# Peripheral.net
KiCad netlist of a schematic drawn in Altium Designer
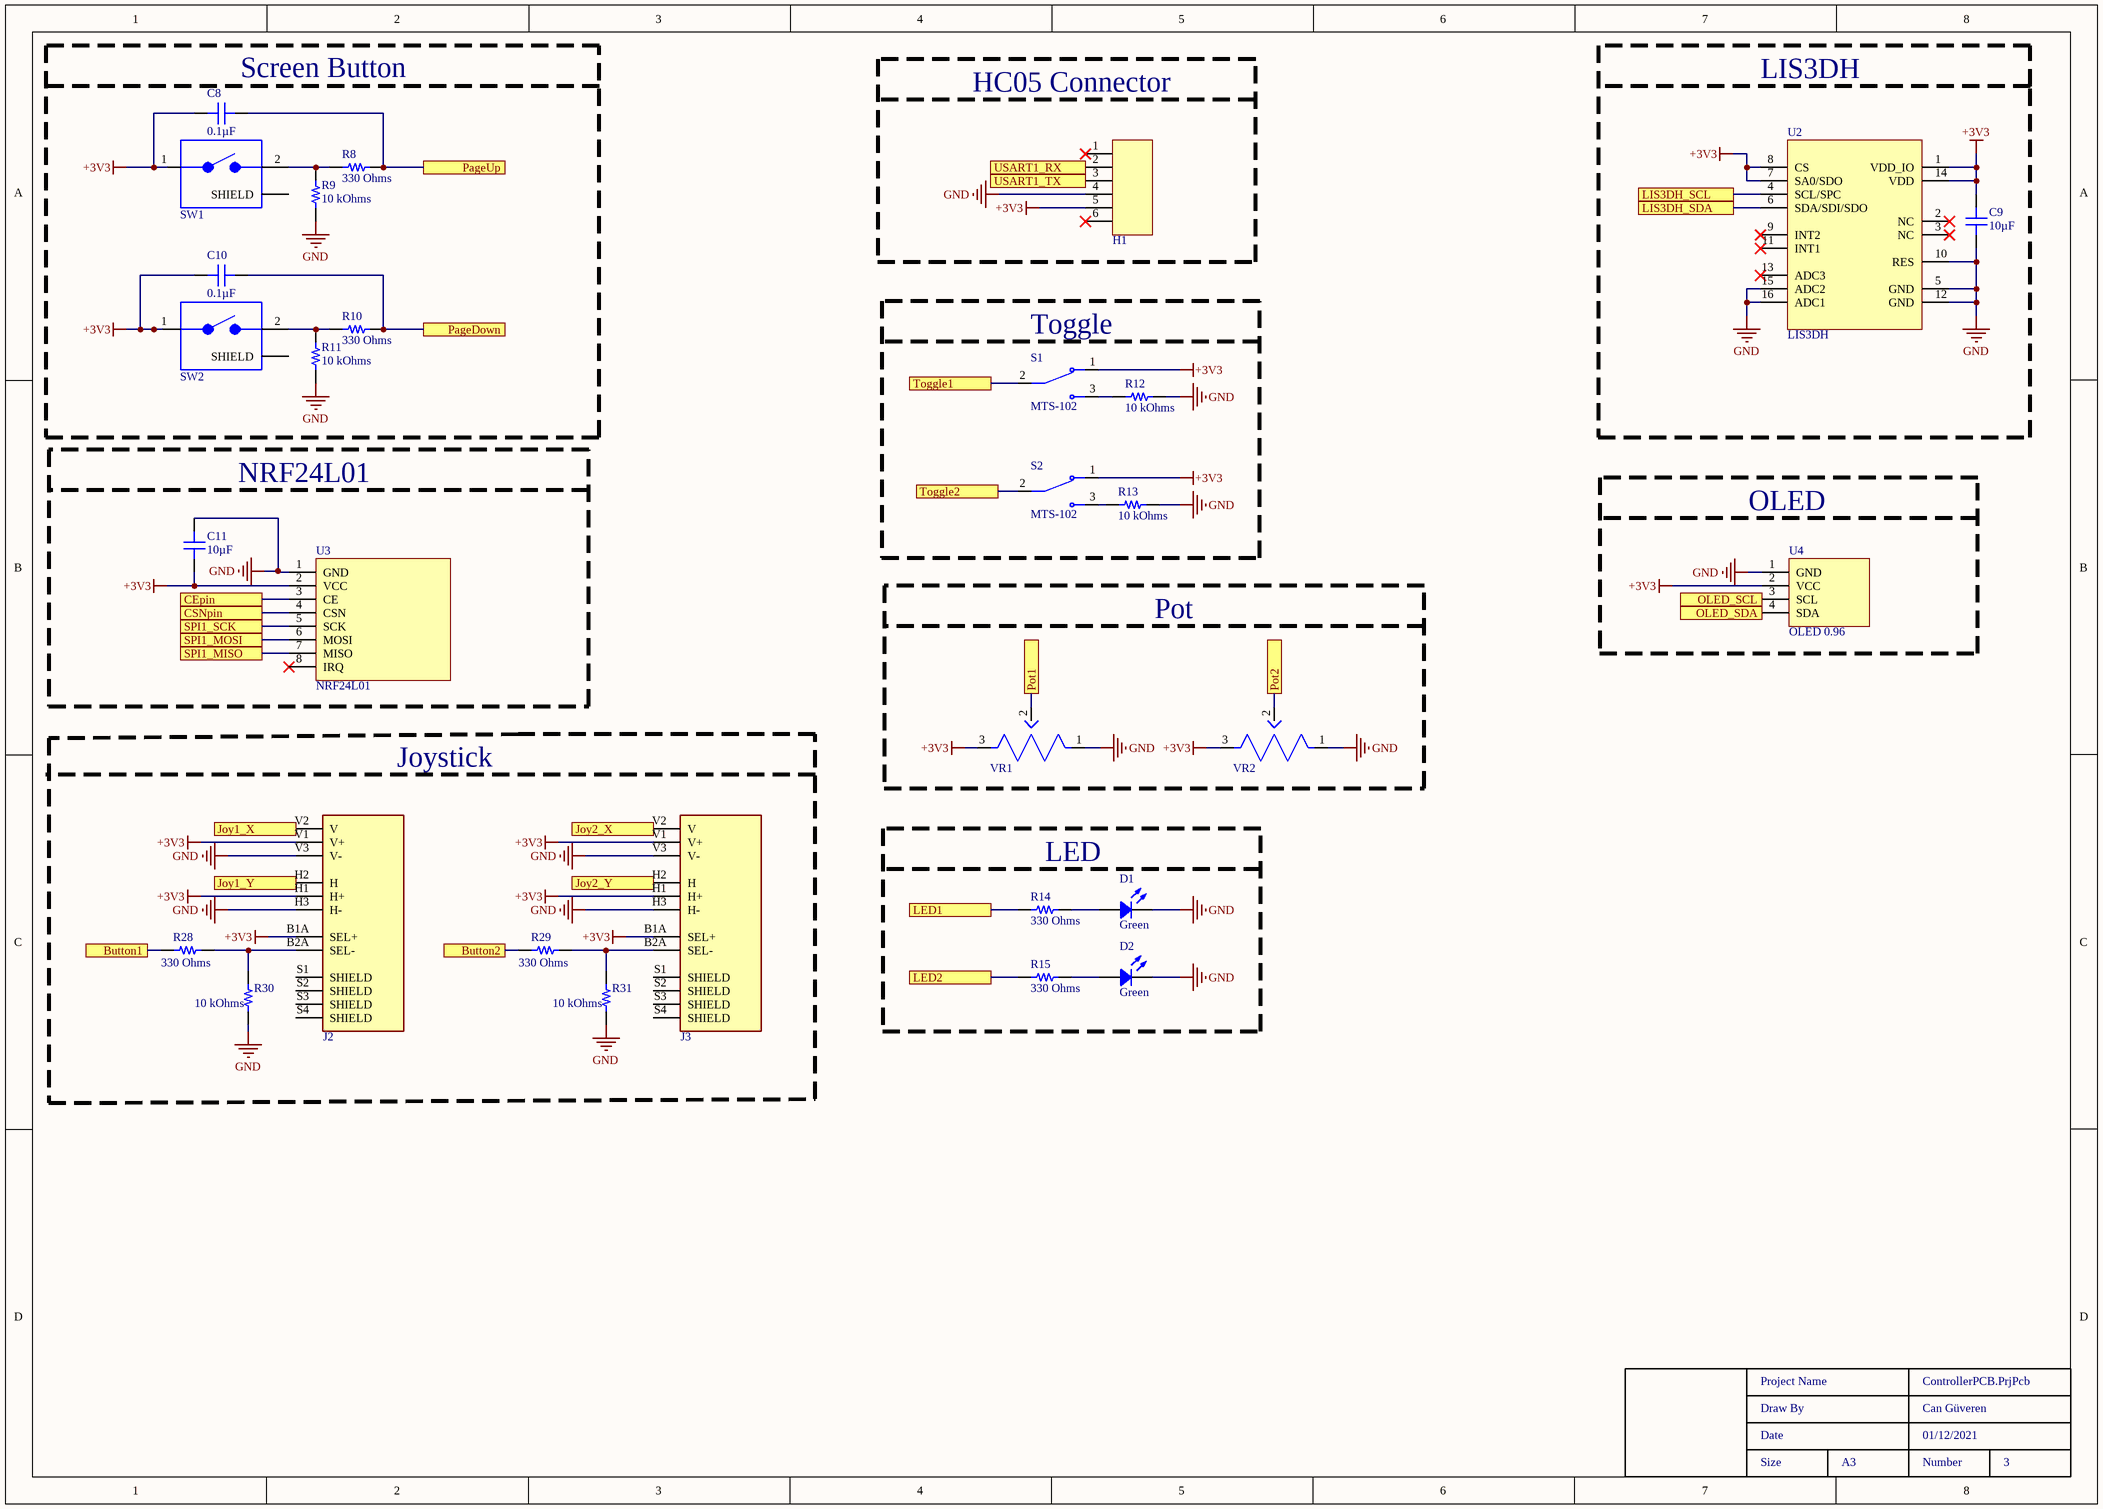
[diagram p0: Peripheral.SchDoc]

(export (version "E")
  (design (tool "Eeschema 10.0.6"))
  (components
    (comp (ref "C8")
      (value "0.1µF")
      (footprint "CAP 0603_1608")
      (description "CAP CER 0.1UF 50V X7R 0603")
      (fields (field (name "PART NUMBER") "C0603C104K5RAC7411") (field (name "MANUFACTURER") "KEMET"))
      (libsource (lib "Celestial Altium Library - altium_library") (part "Capacitor"))
    )
    (comp (ref "C9")
      (value "10µF")
      (footprint "CAP 0603_1608")
      (description "CAP CER 10UF 6.3V X5R 0603")
      (fields
        (field (name "PART NUMBER") "GRM188R60J106ME47D")
        (field (name "MANUFACTURER") "Murata Electronics")
      )
      (libsource (lib "Celestial Altium Library - altium_library") (part "Capacitor"))
    )
    (comp (ref "C10")
      (value "0.1µF")
      (footprint "CAP 0603_1608")
      (description "CAP CER 0.1UF 50V X7R 0603")
      (fields (field (name "PART NUMBER") "C0603C104K5RAC7411") (field (name "MANUFACTURER") "KEMET"))
      (libsource (lib "Celestial Altium Library - altium_library") (part "Capacitor"))
    )
    (comp (ref "C11")
      (value "10µF")
      (footprint "CAP 0603_1608")
      (description "CAP CER 10UF 6.3V X5R 0603")
      (fields
        (field (name "PART NUMBER") "GRM188R60J106ME47D")
        (field (name "MANUFACTURER") "Murata Electronics")
      )
      (libsource (lib "Celestial Altium Library - altium_library") (part "Capacitor"))
    )
    (comp (ref "D1")
      (value "Green")
      (footprint "LED 1206_3216 YELLOW")
      (description "LED YELLOW 1206 SMD")
      (fields (field (name "PART NUMBER") "5990240007F") (field (name "MANUFACTURER") "Dialight"))
      (libsource (lib "Celestial Altium Library - altium_library") (part "LED"))
    )
    (comp (ref "D2")
      (value "Green")
      (footprint "LED 1206_3216 YELLOW")
      (description "LED YELLOW 1206 SMD")
      (fields (field (name "PART NUMBER") "5990240007F") (field (name "MANUFACTURER") "Dialight"))
      (libsource (lib "Celestial Altium Library - altium_library") (part "LED"))
    )
    (comp (ref "H1")
      (value "1x6 Pin Header - Female")
      (footprint "1x6 Pin Header - Female")
      (libsource (lib "MyLibrary_Integrated") (part "1x6 Pin Header - Female"))
    )
    (comp (ref "J2")
      (value "COM-09032")
      (footprint "COM-09032")
      (description "Joystick 10K Ohm 2 Axis Th")
      (fields (field (name "MANUFACTURER") "SparkFun"))
      (libsource (lib "MyLibrary_Integrated") (part "COM-09032"))
    )
    (comp (ref "J3")
      (value "COM-09032")
      (footprint "COM-09032")
      (description "Joystick 10K Ohm 2 Axis Th")
      (fields (field (name "MANUFACTURER") "SparkFun"))
      (libsource (lib "MyLibrary_Integrated") (part "COM-09032"))
    )
    (comp (ref "R8")
      (value "330 Ohms")
      (footprint "RES 0603_1608")
      (description "RES SMD 330 OHM 1% 1/10W 0603")
      (fields (field (name "PART NUMBER") "AC0603FR-07330RL") (field (name "MANUFACTURER") "Yageo"))
      (libsource (lib "Celestial Altium Library - altium_library") (part "Resistor"))
    )
    (comp (ref "R9")
      (value "10 kOhms")
      (footprint "RES 0603_1608")
      (description "RES 10K OHM 0.1% 1/16W 0603")
      (fields
        (field (name "PART NUMBER") "RNCS0603BKE10K0")
        (field (name "MANUFACTURER") "Stackpole Electronics Inc")
      )
      (libsource (lib "Celestial Altium Library - altium_library") (part "Resistor"))
    )
    (comp (ref "R10")
      (value "330 Ohms")
      (footprint "RES 0603_1608")
      (description "RES SMD 330 OHM 1% 1/10W 0603")
      (fields (field (name "PART NUMBER") "AC0603FR-07330RL") (field (name "MANUFACTURER") "Yageo"))
      (libsource (lib "Celestial Altium Library - altium_library") (part "Resistor"))
    )
    (comp (ref "R11")
      (value "10 kOhms")
      (footprint "RES 0603_1608")
      (description "RES 10K OHM 0.1% 1/16W 0603")
      (fields
        (field (name "PART NUMBER") "RNCS0603BKE10K0")
        (field (name "MANUFACTURER") "Stackpole Electronics Inc")
      )
      (libsource (lib "Celestial Altium Library - altium_library") (part "Resistor"))
    )
    (comp (ref "R12")
      (value "10 kOhms")
      (footprint "RES 0603_1608")
      (description "RES 10K OHM 0.1% 1/16W 0603")
      (fields
        (field (name "PART NUMBER") "RNCS0603BKE10K0")
        (field (name "MANUFACTURER") "Stackpole Electronics Inc")
      )
      (libsource (lib "Celestial Altium Library - altium_library") (part "Resistor"))
    )
    (comp (ref "R13")
      (value "10 kOhms")
      (footprint "RES 0603_1608")
      (description "RES 10K OHM 0.1% 1/16W 0603")
      (fields
        (field (name "PART NUMBER") "RNCS0603BKE10K0")
        (field (name "MANUFACTURER") "Stackpole Electronics Inc")
      )
      (libsource (lib "Celestial Altium Library - altium_library") (part "Resistor"))
    )
    (comp (ref "R14")
      (value "330 Ohms")
      (footprint "RES 0603_1608")
      (description "RES SMD 330 OHM 1% 1/10W 0603")
      (fields (field (name "PART NUMBER") "AC0603FR-07330RL") (field (name "MANUFACTURER") "Yageo"))
      (libsource (lib "Celestial Altium Library - altium_library") (part "Resistor"))
    )
    (comp (ref "R15")
      (value "330 Ohms")
      (footprint "RES 0603_1608")
      (description "RES SMD 330 OHM 1% 1/10W 0603")
      (fields (field (name "PART NUMBER") "AC0603FR-07330RL") (field (name "MANUFACTURER") "Yageo"))
      (libsource (lib "Celestial Altium Library - altium_library") (part "Resistor"))
    )
    (comp (ref "R28")
      (value "330 Ohms")
      (footprint "RES 0603_1608")
      (description "RES SMD 330 OHM 1% 1/10W 0603")
      (fields (field (name "PART NUMBER") "AC0603FR-07330RL") (field (name "MANUFACTURER") "Yageo"))
      (libsource (lib "Celestial Altium Library - altium_library") (part "Resistor"))
    )
    (comp (ref "R29")
      (value "330 Ohms")
      (footprint "RES 0603_1608")
      (description "RES SMD 330 OHM 1% 1/10W 0603")
      (fields (field (name "PART NUMBER") "AC0603FR-07330RL") (field (name "MANUFACTURER") "Yageo"))
      (libsource (lib "Celestial Altium Library - altium_library") (part "Resistor"))
    )
    (comp (ref "R30")
      (value "10 kOhms")
      (footprint "RES 0603_1608")
      (description "RES 10K OHM 0.1% 1/16W 0603")
      (fields
        (field (name "PART NUMBER") "RNCS0603BKE10K0")
        (field (name "MANUFACTURER") "Stackpole Electronics Inc")
      )
      (libsource (lib "Celestial Altium Library - altium_library") (part "Resistor"))
    )
    (comp (ref "R31")
      (value "10 kOhms")
      (footprint "RES 0603_1608")
      (description "RES 10K OHM 0.1% 1/16W 0603")
      (fields
        (field (name "PART NUMBER") "RNCS0603BKE10K0")
        (field (name "MANUFACTURER") "Stackpole Electronics Inc")
      )
      (libsource (lib "Celestial Altium Library - altium_library") (part "Resistor"))
    )
    (comp (ref "S1")
      (value "MTS-102")
      (footprint "MTS-102 (Toggle)")
      (libsource (lib "MyLibrary_Integrated") (part "MTS-102"))
    )
    (comp (ref "S2")
      (value "MTS-102")
      (footprint "MTS-102 (Toggle)")
      (libsource (lib "MyLibrary_Integrated") (part "MTS-102"))
    )
    (comp (ref "SW1")
      (value "Switch Tactile, Right Angle")
      (footprint "Tactile Switch")
      (libsource (lib "MyLibrary_Integrated") (part "Switch Tactile, Right Angle"))
    )
    (comp (ref "SW2")
      (value "Switch Tactile, Right Angle")
      (footprint "Tactile Switch")
      (libsource (lib "MyLibrary_Integrated") (part "Switch Tactile, Right Angle"))
    )
    (comp (ref "U2")
      (value "LIS3DH")
      (footprint "VFLGA-16")
      (description "MEMS digital output motion sensor ultra low-power high performance 3-axes \"nano\" accelerometer")
      (fields (field (name "MANUFACTURER") "STMicroelectronics"))
      (libsource (lib "MyLibrary_Integrated") (part "LIS3DH"))
    )
    (comp (ref "U3")
      (value "NRF24L01")
      (footprint "NRF24L01+ PCB")
      (libsource (lib "MyLibrary_Integrated") (part "NRF24L01+ PCB"))
    )
    (comp (ref "U4")
      (value "OLED 0.96")
      (footprint "OLED 0.96")
      (libsource (lib "MyLibrary_Integrated") (part "OLED 0.96"))
    )
    (comp (ref "VR1")
      (value "PTV09A-4225F-B104")
      (footprint "PTV09A-4225F-B104")
      (fields (field (name "MANUFACTURER") "Bourns") (field (name "TOLERANCE") "20%"))
      (libsource (lib "MyLibrary_Integrated") (part "PTV09A-4225F-B104"))
    )
    (comp (ref "VR2")
      (value "PTV09A-4225F-B104")
      (footprint "PTV09A-4225F-B104")
      (fields (field (name "MANUFACTURER") "Bourns") (field (name "TOLERANCE") "20%"))
      (libsource (lib "MyLibrary_Integrated") (part "PTV09A-4225F-B104"))
    )
  )
  (nets
    (net (code "1") (name "+3V3") (class "Default")
      (node (ref "C10") (pin "1") (pinfunction "1_1") (pintype "passive"))
      (node (ref "C11") (pin "1") (pinfunction "1_1") (pintype "passive"))
      (node (ref "C8") (pin "1") (pinfunction "1_1") (pintype "passive"))
      (node (ref "C9") (pin "2") (pinfunction "2_2") (pintype "passive"))
      (node (ref "H1") (pin "5") (pinfunction "4_5") (pintype "passive"))
      (node (ref "J2") (pin "B1A") (pinfunction "SEL+_B1A") (pintype "passive"))
      (node (ref "J2") (pin "H1") (pinfunction "H+_H1") (pintype "passive"))
      (node (ref "J2") (pin "V1") (pinfunction "V+_V1") (pintype "passive"))
      (node (ref "J3") (pin "B1A") (pinfunction "SEL+_B1A") (pintype "passive"))
      (node (ref "J3") (pin "H1") (pinfunction "H+_H1") (pintype "passive"))
      (node (ref "J3") (pin "V1") (pinfunction "V+_V1") (pintype "passive"))
      (node (ref "S1") (pin "1") (pinfunction "1_1") (pintype "passive"))
      (node (ref "S2") (pin "1") (pinfunction "1_1") (pintype "passive"))
      (node (ref "SW1") (pin "1") (pinfunction "1_1") (pintype "passive"))
      (node (ref "SW2") (pin "1") (pinfunction "1_1") (pintype "passive"))
      (node (ref "U2") (pin "1") (pinfunction "VDD_IO_1") (pintype "passive"))
      (node (ref "U2") (pin "14") (pinfunction "VDD_14") (pintype "passive"))
      (node (ref "U2") (pin "7") (pinfunction "SA0/SDO_7") (pintype "passive"))
      (node (ref "U2") (pin "8") (pinfunction "CS_8") (pintype "passive"))
      (node (ref "U3") (pin "2") (pinfunction "VCC_2") (pintype "passive"))
      (node (ref "U4") (pin "2") (pinfunction "VCC_2") (pintype "passive"))
      (node (ref "VR1") (pin "3") (pinfunction "3_3") (pintype "passive"))
      (node (ref "VR2") (pin "3") (pinfunction "3_3") (pintype "passive"))
    )
    (net (code "2") (name "/Button1") (class "Default")
      (node (ref "R28") (pin "1") (pinfunction "1_1") (pintype "passive"))
    )
    (net (code "3") (name "/Button2") (class "Default")
      (node (ref "R29") (pin "1") (pinfunction "1_1") (pintype "passive"))
    )
    (net (code "4") (name "/CEpin") (class "Default")
      (node (ref "U3") (pin "3") (pinfunction "CE_3") (pintype "passive"))
    )
    (net (code "5") (name "/CSNpin") (class "Default")
      (node (ref "U3") (pin "4") (pinfunction "CSN_4") (pintype "passive"))
    )
    (net (code "6") (name "/Joy1_X") (class "Default")
      (node (ref "J2") (pin "V2") (pinfunction "V_V2") (pintype "passive"))
    )
    (net (code "7") (name "/Joy1_Y") (class "Default")
      (node (ref "J2") (pin "H2") (pinfunction "H_H2") (pintype "passive"))
    )
    (net (code "8") (name "/Joy2_X") (class "Default")
      (node (ref "J3") (pin "V2") (pinfunction "V_V2") (pintype "passive"))
    )
    (net (code "9") (name "/Joy2_Y") (class "Default")
      (node (ref "J3") (pin "H2") (pinfunction "H_H2") (pintype "passive"))
    )
    (net (code "10") (name "/LED1") (class "Default")
      (node (ref "R14") (pin "1") (pinfunction "1_1") (pintype "passive"))
    )
    (net (code "11") (name "/LED2") (class "Default")
      (node (ref "R15") (pin "1") (pinfunction "1_1") (pintype "passive"))
    )
    (net (code "12") (name "/LIS3DH_SCL") (class "Default")
      (node (ref "U2") (pin "4") (pinfunction "SCL/SPC_4") (pintype "passive"))
    )
    (net (code "13") (name "/LIS3DH_SDA") (class "Default")
      (node (ref "U2") (pin "6") (pinfunction "SDA/SDI/SDO_6") (pintype "passive"))
    )
    (net (code "14") (name "/OLED_SCL") (class "Default")
      (node (ref "U4") (pin "3") (pinfunction "SCL_3") (pintype "passive"))
    )
    (net (code "15") (name "/OLED_SDA") (class "Default")
      (node (ref "U4") (pin "4") (pinfunction "SDA_4") (pintype "passive"))
    )
    (net (code "16") (name "/PageDown") (class "Default")
      (node (ref "C10") (pin "2") (pinfunction "2_2") (pintype "passive"))
      (node (ref "R10") (pin "2") (pinfunction "2_2") (pintype "passive"))
    )
    (net (code "17") (name "/PageUp") (class "Default")
      (node (ref "C8") (pin "2") (pinfunction "2_2") (pintype "passive"))
      (node (ref "R8") (pin "2") (pinfunction "2_2") (pintype "passive"))
    )
    (net (code "18") (name "/Pot1") (class "Default")
      (node (ref "VR1") (pin "2") (pinfunction "2_2") (pintype "passive"))
    )
    (net (code "19") (name "/Pot2") (class "Default")
      (node (ref "VR2") (pin "2") (pinfunction "2_2") (pintype "passive"))
    )
    (net (code "20") (name "/SPI1_MISO") (class "Default")
      (node (ref "U3") (pin "7") (pinfunction "MISO_7") (pintype "passive"))
    )
    (net (code "21") (name "/SPI1_MOSI") (class "Default")
      (node (ref "U3") (pin "6") (pinfunction "MOSI_6") (pintype "passive"))
    )
    (net (code "22") (name "/SPI1_SCK") (class "Default")
      (node (ref "U3") (pin "5") (pinfunction "SCK_5") (pintype "passive"))
    )
    (net (code "23") (name "/Toggle1") (class "Default")
      (node (ref "S1") (pin "2") (pinfunction "2_2") (pintype "passive"))
    )
    (net (code "24") (name "/Toggle2") (class "Default")
      (node (ref "S2") (pin "2") (pinfunction "2_2") (pintype "passive"))
    )
    (net (code "25") (name "/USART1_RX") (class "Default")
      (node (ref "H1") (pin "2") (pinfunction "1_2") (pintype "passive"))
    )
    (net (code "26") (name "/USART1_TX") (class "Default")
      (node (ref "H1") (pin "3") (pinfunction "2_3") (pintype "passive"))
    )
    (net (code "27") (name "GND") (class "Default")
      (node (ref "C11") (pin "2") (pinfunction "2_2") (pintype "passive"))
      (node (ref "C9") (pin "1") (pinfunction "1_1") (pintype "passive"))
      (node (ref "D1") (pin "2") (pinfunction "2_2") (pintype "passive"))
      (node (ref "D2") (pin "2") (pinfunction "2_2") (pintype "passive"))
      (node (ref "H1") (pin "4") (pinfunction "3_4") (pintype "passive"))
      (node (ref "J2") (pin "H3") (pinfunction "H-_H3") (pintype "passive"))
      (node (ref "J2") (pin "V3") (pinfunction "V-_V3") (pintype "passive"))
      (node (ref "J3") (pin "H3") (pinfunction "H-_H3") (pintype "passive"))
      (node (ref "J3") (pin "V3") (pinfunction "V-_V3") (pintype "passive"))
      (node (ref "R11") (pin "1") (pinfunction "1_1") (pintype "passive"))
      (node (ref "R12") (pin "1") (pinfunction "1_1") (pintype "passive"))
      (node (ref "R13") (pin "1") (pinfunction "1_1") (pintype "passive"))
      (node (ref "R30") (pin "1") (pinfunction "1_1") (pintype "passive"))
      (node (ref "R31") (pin "1") (pinfunction "1_1") (pintype "passive"))
      (node (ref "R9") (pin "1") (pinfunction "1_1") (pintype "passive"))
      (node (ref "U2") (pin "10") (pinfunction "RES_10") (pintype "passive"))
      (node (ref "U2") (pin "12") (pinfunction "GND_12") (pintype "passive"))
      (node (ref "U2") (pin "15") (pinfunction "ADC2_15") (pintype "passive"))
      (node (ref "U2") (pin "16") (pinfunction "ADC1_16") (pintype "passive"))
      (node (ref "U2") (pin "5") (pinfunction "GND_5") (pintype "passive"))
      (node (ref "U3") (pin "1") (pinfunction "GND_1") (pintype "passive"))
      (node (ref "U4") (pin "1") (pinfunction "GND_1") (pintype "passive"))
      (node (ref "VR1") (pin "1") (pinfunction "1_1") (pintype "passive"))
      (node (ref "VR2") (pin "1") (pinfunction "1_1") (pintype "passive"))
    )
    (net (code "28") (name "Net-(D1-Pad1)") (class "Default")
      (node (ref "D1") (pin "1") (pinfunction "1_1") (pintype "passive"))
      (node (ref "R14") (pin "2") (pinfunction "2_2") (pintype "passive"))
    )
    (net (code "29") (name "Net-(D2-Pad1)") (class "Default")
      (node (ref "D2") (pin "1") (pinfunction "1_1") (pintype "passive"))
      (node (ref "R15") (pin "2") (pinfunction "2_2") (pintype "passive"))
    )
    (net (code "30") (name "Net-(J2-SEL-)") (class "Default")
      (node (ref "J2") (pin "B2A") (pinfunction "SEL-_B2A") (pintype "passive"))
      (node (ref "R28") (pin "2") (pinfunction "2_2") (pintype "passive"))
      (node (ref "R30") (pin "2") (pinfunction "2_2") (pintype "passive"))
    )
    (net (code "31") (name "Net-(J3-SEL-)") (class "Default")
      (node (ref "J3") (pin "B2A") (pinfunction "SEL-_B2A") (pintype "passive"))
      (node (ref "R29") (pin "2") (pinfunction "2_2") (pintype "passive"))
      (node (ref "R31") (pin "2") (pinfunction "2_2") (pintype "passive"))
    )
    (net (code "32") (name "Net-(R8-Pad1)") (class "Default")
      (node (ref "R8") (pin "1") (pinfunction "1_1") (pintype "passive"))
      (node (ref "R9") (pin "2") (pinfunction "2_2") (pintype "passive"))
      (node (ref "SW1") (pin "2") (pinfunction "2_2") (pintype "passive"))
    )
    (net (code "33") (name "Net-(R10-Pad1)") (class "Default")
      (node (ref "R10") (pin "1") (pinfunction "1_1") (pintype "passive"))
      (node (ref "R11") (pin "2") (pinfunction "2_2") (pintype "passive"))
      (node (ref "SW2") (pin "2") (pinfunction "2_2") (pintype "passive"))
    )
    (net (code "34") (name "Net-(R12-Pad2)") (class "Default")
      (node (ref "R12") (pin "2") (pinfunction "2_2") (pintype "passive"))
      (node (ref "S1") (pin "3") (pinfunction "3_3") (pintype "passive"))
    )
    (net (code "35") (name "Net-(R13-Pad2)") (class "Default")
      (node (ref "R13") (pin "2") (pinfunction "2_2") (pintype "passive"))
      (node (ref "S2") (pin "3") (pinfunction "3_3") (pintype "passive"))
    )
    (net (code "36") (name "Net-(SW1-SHIELD-PadS1)") (class "Default")
      (node (ref "SW1") (pin "S1") (pinfunction "SHIELD_S1") (pintype "passive"))
      (node (ref "SW1") (pin "S2") (pinfunction "SHIELD_S2") (pintype "passive"))
    )
    (net (code "37") (name "Net-(SW2-SHIELD-PadS1)") (class "Default")
      (node (ref "SW2") (pin "S1") (pinfunction "SHIELD_S1") (pintype "passive"))
      (node (ref "SW2") (pin "S2") (pinfunction "SHIELD_S2") (pintype "passive"))
    )
    (net (code "38") (name "unconnected-(H1-0-Pad1)") (class "Default")
      (node (ref "H1") (pin "1") (pinfunction "0_1") (pintype "passive+no_connect"))
    )
    (net (code "39") (name "unconnected-(H1-5-Pad6)") (class "Default")
      (node (ref "H1") (pin "6") (pinfunction "5_6") (pintype "passive+no_connect"))
    )
    (net (code "40") (name "unconnected-(J2-SHIELD-PadS1)") (class "Default")
      (node (ref "J2") (pin "S1") (pinfunction "SHIELD_S1") (pintype "passive"))
    )
    (net (code "41") (name "unconnected-(J2-SHIELD-PadS2)") (class "Default")
      (node (ref "J2") (pin "S2") (pinfunction "SHIELD_S2") (pintype "passive"))
    )
    (net (code "42") (name "unconnected-(J2-SHIELD-PadS3)") (class "Default")
      (node (ref "J2") (pin "S3") (pinfunction "SHIELD_S3") (pintype "passive"))
    )
    (net (code "43") (name "unconnected-(J2-SHIELD-PadS4)") (class "Default")
      (node (ref "J2") (pin "S4") (pinfunction "SHIELD_S4") (pintype "passive"))
    )
    (net (code "44") (name "unconnected-(J3-SHIELD-PadS1)") (class "Default")
      (node (ref "J3") (pin "S1") (pinfunction "SHIELD_S1") (pintype "passive"))
    )
    (net (code "45") (name "unconnected-(J3-SHIELD-PadS2)") (class "Default")
      (node (ref "J3") (pin "S2") (pinfunction "SHIELD_S2") (pintype "passive"))
    )
    (net (code "46") (name "unconnected-(J3-SHIELD-PadS3)") (class "Default")
      (node (ref "J3") (pin "S3") (pinfunction "SHIELD_S3") (pintype "passive"))
    )
    (net (code "47") (name "unconnected-(J3-SHIELD-PadS4)") (class "Default")
      (node (ref "J3") (pin "S4") (pinfunction "SHIELD_S4") (pintype "passive"))
    )
    (net (code "48") (name "unconnected-(U2-ADC3-Pad13)") (class "Default")
      (node (ref "U2") (pin "13") (pinfunction "ADC3_13") (pintype "passive+no_connect"))
    )
    (net (code "49") (name "unconnected-(U2-INT1-Pad11)") (class "Default")
      (node (ref "U2") (pin "11") (pinfunction "INT1_11") (pintype "passive+no_connect"))
    )
    (net (code "50") (name "unconnected-(U2-INT2-Pad9)") (class "Default")
      (node (ref "U2") (pin "9") (pinfunction "INT2_9") (pintype "passive+no_connect"))
    )
    (net (code "51") (name "unconnected-(U2-NC-Pad2)") (class "Default")
      (node (ref "U2") (pin "2") (pinfunction "NC_2") (pintype "passive+no_connect"))
    )
    (net (code "52") (name "unconnected-(U2-NC-Pad3)") (class "Default")
      (node (ref "U2") (pin "3") (pinfunction "NC_3") (pintype "passive+no_connect"))
    )
    (net (code "53") (name "unconnected-(U3-IRQ-Pad8)") (class "Default")
      (node (ref "U3") (pin "8") (pinfunction "IRQ_8") (pintype "passive+no_connect"))
    )
  )
)
